# BATT_FLEX8.net
KiCad netlist of a schematic drawn in EAGLE
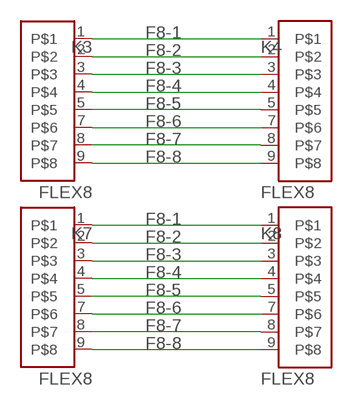
[diagram p0: schematic, sheet 1]

(export (version "E")
  (design (tool "Eeschema 10.0.6"))
  (components
    (comp (ref "K3")
      (value "FLEX8")
      (footprint "eagle-import:FLEX8")
      (libsource (lib "eagle-import") (part "FLEX8"))
    )
    (comp (ref "K4")
      (value "FLEX8")
      (footprint "eagle-import:FLEX8")
      (libsource (lib "eagle-import") (part "FLEX8"))
    )
    (comp (ref "K7")
      (value "FLEX8")
      (footprint "eagle-import:FLEX8")
      (libsource (lib "eagle-import") (part "FLEX8"))
    )
    (comp (ref "K8")
      (value "FLEX8")
      (footprint "eagle-import:FLEX8")
      (libsource (lib "eagle-import") (part "FLEX8"))
    )
  )
  (nets
    (net (code "1") (name "/F8-1") (class "Default")
      (node (ref "K3") (pin "1") (pinfunction "P$1_1") (pintype "bidirectional"))
      (node (ref "K4") (pin "1") (pinfunction "P$1_1") (pintype "bidirectional"))
      (node (ref "K7") (pin "1") (pinfunction "P$1_1") (pintype "bidirectional"))
      (node (ref "K8") (pin "1") (pinfunction "P$1_1") (pintype "bidirectional"))
    )
    (net (code "2") (name "/F8-2") (class "Default")
      (node (ref "K3") (pin "2") (pinfunction "P$2_2") (pintype "bidirectional"))
      (node (ref "K4") (pin "2") (pinfunction "P$2_2") (pintype "bidirectional"))
      (node (ref "K7") (pin "2") (pinfunction "P$2_2") (pintype "bidirectional"))
      (node (ref "K8") (pin "2") (pinfunction "P$2_2") (pintype "bidirectional"))
    )
    (net (code "3") (name "/F8-3") (class "Default")
      (node (ref "K3") (pin "3") (pinfunction "P$3_3") (pintype "bidirectional"))
      (node (ref "K4") (pin "3") (pinfunction "P$3_3") (pintype "bidirectional"))
      (node (ref "K7") (pin "3") (pinfunction "P$3_3") (pintype "bidirectional"))
      (node (ref "K8") (pin "3") (pinfunction "P$3_3") (pintype "bidirectional"))
    )
    (net (code "4") (name "/F8-4") (class "Default")
      (node (ref "K3") (pin "4") (pinfunction "P$4_4") (pintype "bidirectional"))
      (node (ref "K4") (pin "4") (pinfunction "P$4_4") (pintype "bidirectional"))
      (node (ref "K7") (pin "4") (pinfunction "P$4_4") (pintype "bidirectional"))
      (node (ref "K8") (pin "4") (pinfunction "P$4_4") (pintype "bidirectional"))
    )
    (net (code "5") (name "/F8-5") (class "Default")
      (node (ref "K3") (pin "5") (pinfunction "P$5_5") (pintype "bidirectional"))
      (node (ref "K4") (pin "5") (pinfunction "P$5_5") (pintype "bidirectional"))
      (node (ref "K7") (pin "5") (pinfunction "P$5_5") (pintype "bidirectional"))
      (node (ref "K8") (pin "5") (pinfunction "P$5_5") (pintype "bidirectional"))
    )
    (net (code "6") (name "/F8-6") (class "Default")
      (node (ref "K3") (pin "7") (pinfunction "P$6_7") (pintype "bidirectional"))
      (node (ref "K4") (pin "7") (pinfunction "P$6_7") (pintype "bidirectional"))
      (node (ref "K7") (pin "7") (pinfunction "P$6_7") (pintype "bidirectional"))
      (node (ref "K8") (pin "7") (pinfunction "P$6_7") (pintype "bidirectional"))
    )
    (net (code "7") (name "/F8-7") (class "Default")
      (node (ref "K3") (pin "8") (pinfunction "P$7_8") (pintype "bidirectional"))
      (node (ref "K4") (pin "8") (pinfunction "P$7_8") (pintype "bidirectional"))
      (node (ref "K7") (pin "8") (pinfunction "P$7_8") (pintype "bidirectional"))
      (node (ref "K8") (pin "8") (pinfunction "P$7_8") (pintype "bidirectional"))
    )
    (net (code "8") (name "/F8-8") (class "Default")
      (node (ref "K3") (pin "9") (pinfunction "P$8_9") (pintype "bidirectional"))
      (node (ref "K4") (pin "9") (pinfunction "P$8_9") (pintype "bidirectional"))
      (node (ref "K7") (pin "9") (pinfunction "P$8_9") (pintype "bidirectional"))
      (node (ref "K8") (pin "9") (pinfunction "P$8_9") (pintype "bidirectional"))
    )
  )
)
